# Sheet2.net
KiCad netlist of a schematic drawn in Altium Designer
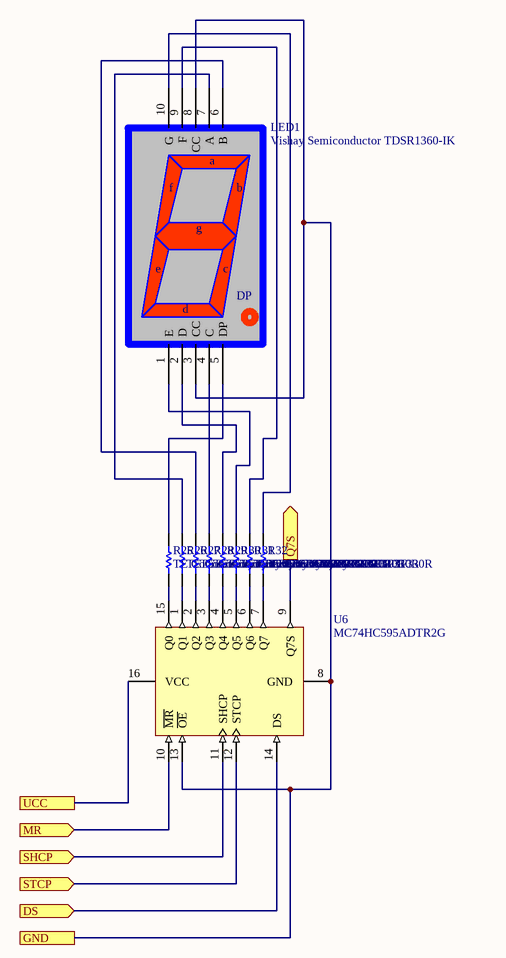
[diagram p0: Sheet2.SchDoc]

(export (version "E")
  (design (tool "Eeschema 10.0.6"))
  (components
    (comp (ref "LED1")
      (value "Vishay Semiconductor TDSR1360-IK")
      (footprint "PCB-wjfw9shywxa82n8451hf-1")
      (description "Displays Dot Matrix Module 1DIGIT 8LED Red 10-Pin DIP Tube")
      (fields (field (name "MANUFACTURER PART NUMBER") "TDSR1360-IK"))
      (libsource (lib "My Personal Space") (part "SYM-f4ae3c33d6e22b69-1"))
    )
    (comp (ref "R25")
      (value "TE Connectivity CRG0603F330R")
      (footprint "RESC1608X55X30NL15T15")
      (description "Res Thick Film 0603 330 Ohm 1% 0.1W(1/10W) ±100ppm/C Pad SMD T/R")
      (fields (field (name "MANUFACTURER PART NUMBER") "CRG0603F330R"))
      (libsource (lib "My Personal Space") (part "RES-2"))
    )
    (comp (ref "R26")
      (value "TE Connectivity CRG0603F330R")
      (footprint "RESC1608X55X30NL15T15")
      (description "Res Thick Film 0603 330 Ohm 1% 0.1W(1/10W) ±100ppm/C Pad SMD T/R")
      (fields (field (name "MANUFACTURER PART NUMBER") "CRG0603F330R"))
      (libsource (lib "My Personal Space") (part "RES-2"))
    )
    (comp (ref "R27")
      (value "TE Connectivity CRG0603F330R")
      (footprint "RESC1608X55X30NL15T15")
      (description "Res Thick Film 0603 330 Ohm 1% 0.1W(1/10W) ±100ppm/C Pad SMD T/R")
      (fields (field (name "MANUFACTURER PART NUMBER") "CRG0603F330R"))
      (libsource (lib "My Personal Space") (part "RES-2"))
    )
    (comp (ref "R28")
      (value "TE Connectivity CRG0603F330R")
      (footprint "RESC1608X55X30NL15T15")
      (description "Res Thick Film 0603 330 Ohm 1% 0.1W(1/10W) ±100ppm/C Pad SMD T/R")
      (fields (field (name "MANUFACTURER PART NUMBER") "CRG0603F330R"))
      (libsource (lib "My Personal Space") (part "RES-2"))
    )
    (comp (ref "R29")
      (value "TE Connectivity CRG0603F330R")
      (footprint "RESC1608X55X30NL15T15")
      (description "Res Thick Film 0603 330 Ohm 1% 0.1W(1/10W) ±100ppm/C Pad SMD T/R")
      (fields (field (name "MANUFACTURER PART NUMBER") "CRG0603F330R"))
      (libsource (lib "My Personal Space") (part "RES-2"))
    )
    (comp (ref "R30")
      (value "TE Connectivity CRG0603F330R")
      (footprint "RESC1608X55X30NL15T15")
      (description "Res Thick Film 0603 330 Ohm 1% 0.1W(1/10W) ±100ppm/C Pad SMD T/R")
      (fields (field (name "MANUFACTURER PART NUMBER") "CRG0603F330R"))
      (libsource (lib "My Personal Space") (part "RES-2"))
    )
    (comp (ref "R31")
      (value "TE Connectivity CRG0603F330R")
      (footprint "RESC1608X55X30NL15T15")
      (description "Res Thick Film 0603 330 Ohm 1% 0.1W(1/10W) ±100ppm/C Pad SMD T/R")
      (fields (field (name "MANUFACTURER PART NUMBER") "CRG0603F330R"))
      (libsource (lib "My Personal Space") (part "RES-2"))
    )
    (comp (ref "R32")
      (value "TE Connectivity CRG0603F330R")
      (footprint "RESC1608X55X30NL15T15")
      (description "Res Thick Film 0603 330 Ohm 1% 0.1W(1/10W) ±100ppm/C Pad SMD T/R")
      (fields (field (name "MANUFACTURER PART NUMBER") "CRG0603F330R"))
      (libsource (lib "My Personal Space") (part "RES-2"))
    )
    (comp (ref "U6")
      (value "MC74HC595ADTR2G")
      (footprint "MC74HC595ADTR2G-Footprint-1")
      (description "Shift Shift Register 1 Element 8 Bit 16-TSSOP")
      (libsource (lib "My Personal Space") (part "MC74HC595ADTR2G-Symbol-1"))
    )
  )
  (nets
    (net (code "1") (name "/DS") (class "Default")
      (node (ref "U6") (pin "14") (pinfunction "DS_14") (pintype "input"))
    )
    (net (code "2") (name "/GND") (class "Default")
      (node (ref "LED1") (pin "3") (pinfunction "CC_3") (pintype "passive"))
      (node (ref "LED1") (pin "8") (pinfunction "CC_8") (pintype "passive"))
      (node (ref "U6") (pin "13") (pinfunction "~{OE}_13") (pintype "input"))
      (node (ref "U6") (pin "8") (pinfunction "GND_8") (pintype "power_in"))
    )
    (net (code "3") (name "/MR") (class "Default")
      (node (ref "U6") (pin "10") (pinfunction "~{MR}_10") (pintype "input"))
    )
    (net (code "4") (name "/Q7S") (class "Default")
      (node (ref "U6") (pin "9") (pinfunction "Q7S_9") (pintype "output"))
    )
    (net (code "5") (name "/SHCP") (class "Default")
      (node (ref "U6") (pin "11") (pinfunction "SHCP_11") (pintype "input"))
    )
    (net (code "6") (name "/STCP") (class "Default")
      (node (ref "U6") (pin "12") (pinfunction "STCP_12") (pintype "input"))
    )
    (net (code "7") (name "/UCC") (class "Default")
      (node (ref "U6") (pin "16") (pinfunction "VCC_16") (pintype "power_in"))
    )
    (net (code "8") (name "Net-(LED1-A)") (class "Default")
      (node (ref "LED1") (pin "7") (pinfunction "A_7") (pintype "passive"))
      (node (ref "R26") (pin "2") (pinfunction "2_2") (pintype "passive"))
    )
    (net (code "9") (name "Net-(LED1-B)") (class "Default")
      (node (ref "LED1") (pin "6") (pinfunction "B_6") (pintype "passive"))
      (node (ref "R27") (pin "2") (pinfunction "2_2") (pintype "passive"))
    )
    (net (code "10") (name "Net-(LED1-C)") (class "Default")
      (node (ref "LED1") (pin "4") (pinfunction "C_4") (pintype "passive"))
      (node (ref "R28") (pin "2") (pinfunction "2_2") (pintype "passive"))
    )
    (net (code "11") (name "Net-(LED1-D)") (class "Default")
      (node (ref "LED1") (pin "2") (pinfunction "D_2") (pintype "passive"))
      (node (ref "R29") (pin "2") (pinfunction "2_2") (pintype "passive"))
    )
    (net (code "12") (name "Net-(LED1-DP)") (class "Default")
      (node (ref "LED1") (pin "5") (pinfunction "DP_5") (pintype "passive"))
      (node (ref "R25") (pin "2") (pinfunction "2_2") (pintype "passive"))
    )
    (net (code "13") (name "Net-(LED1-E)") (class "Default")
      (node (ref "LED1") (pin "1") (pinfunction "E_1") (pintype "passive"))
      (node (ref "R30") (pin "2") (pinfunction "2_2") (pintype "passive"))
    )
    (net (code "14") (name "Net-(LED1-F)") (class "Default")
      (node (ref "LED1") (pin "9") (pinfunction "F_9") (pintype "passive"))
      (node (ref "R31") (pin "2") (pinfunction "2_2") (pintype "passive"))
    )
    (net (code "15") (name "Net-(LED1-G)") (class "Default")
      (node (ref "LED1") (pin "10") (pinfunction "G_10") (pintype "passive"))
      (node (ref "R32") (pin "2") (pinfunction "2_2") (pintype "passive"))
    )
    (net (code "16") (name "Net-(U6-Q0)") (class "Default")
      (node (ref "R25") (pin "1") (pinfunction "1_1") (pintype "passive"))
      (node (ref "U6") (pin "15") (pinfunction "Q0_15") (pintype "output"))
    )
    (net (code "17") (name "Net-(U6-Q1)") (class "Default")
      (node (ref "R26") (pin "1") (pinfunction "1_1") (pintype "passive"))
      (node (ref "U6") (pin "1") (pinfunction "Q1_1") (pintype "output"))
    )
    (net (code "18") (name "Net-(U6-Q2)") (class "Default")
      (node (ref "R27") (pin "1") (pinfunction "1_1") (pintype "passive"))
      (node (ref "U6") (pin "2") (pinfunction "Q2_2") (pintype "output"))
    )
    (net (code "19") (name "Net-(U6-Q3)") (class "Default")
      (node (ref "R28") (pin "1") (pinfunction "1_1") (pintype "passive"))
      (node (ref "U6") (pin "3") (pinfunction "Q3_3") (pintype "output"))
    )
    (net (code "20") (name "Net-(U6-Q4)") (class "Default")
      (node (ref "R29") (pin "1") (pinfunction "1_1") (pintype "passive"))
      (node (ref "U6") (pin "4") (pinfunction "Q4_4") (pintype "output"))
    )
    (net (code "21") (name "Net-(U6-Q5)") (class "Default")
      (node (ref "R30") (pin "1") (pinfunction "1_1") (pintype "passive"))
      (node (ref "U6") (pin "5") (pinfunction "Q5_5") (pintype "output"))
    )
    (net (code "22") (name "Net-(U6-Q6)") (class "Default")
      (node (ref "R31") (pin "1") (pinfunction "1_1") (pintype "passive"))
      (node (ref "U6") (pin "6") (pinfunction "Q6_6") (pintype "output"))
    )
    (net (code "23") (name "Net-(U6-Q7)") (class "Default")
      (node (ref "R32") (pin "1") (pinfunction "1_1") (pintype "passive"))
      (node (ref "U6") (pin "7") (pinfunction "Q7_7") (pintype "output"))
    )
  )
)
